# AC_REMOTE.net
KiCad netlist of a schematic drawn in Altium Designer
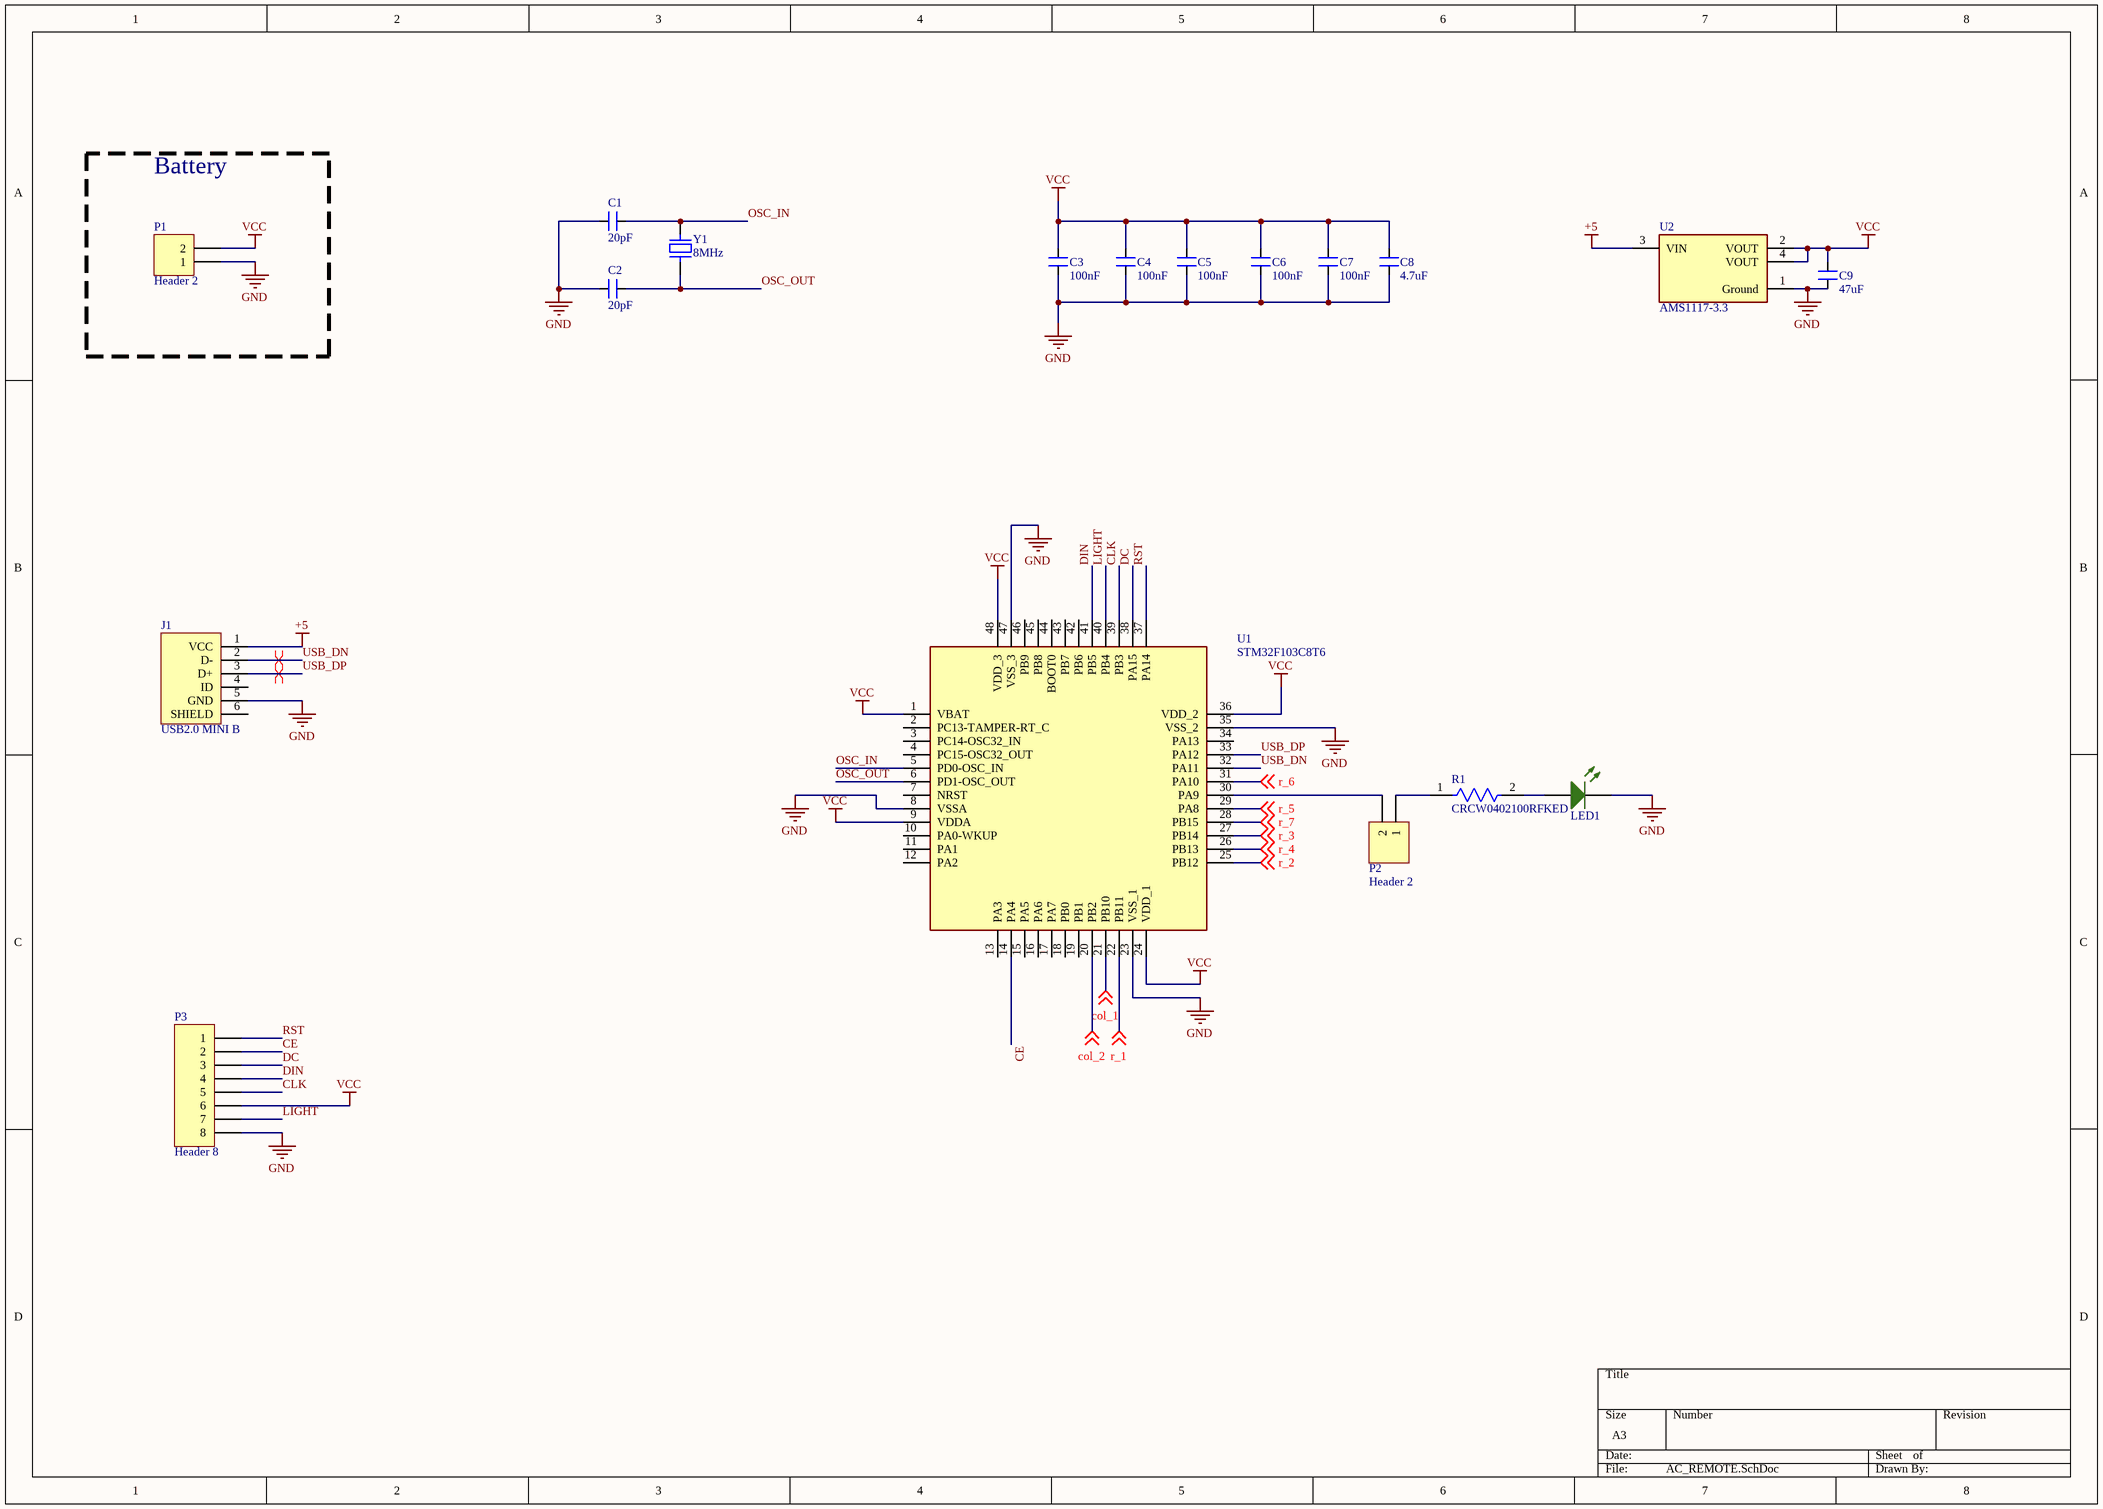
[diagram p0: AC_REMOTE.SchDoc]

(export (version "E")
  (design (tool "Eeschema 10.0.6"))
  (components
    (comp (ref "C1")
      (value "20pF")
      (footprint "CAP_0805")
      (description "±10% 50V Ceramic Capacitor C0G, NP0 0805 (2012 Metric)")
      (fields
        (field (name "MANUFACTURER") "AVX Corporation")
        (field (name "MANUFACTURER PART NUMBER") "08055A200KAT2A")
      )
      (libsource (lib "ESTEEMPCBLIB") (part "CAP_20pF-50V-10%-0805"))
    )
    (comp (ref "C2")
      (value "20pF")
      (footprint "CAP_0805")
      (description "±10% 50V Ceramic Capacitor C0G, NP0 0805 (2012 Metric)")
      (fields
        (field (name "MANUFACTURER") "AVX Corporation")
        (field (name "MANUFACTURER PART NUMBER") "08055A200KAT2A")
      )
      (libsource (lib "ESTEEMPCBLIB") (part "CAP_20pF-50V-10%-0805"))
    )
    (comp (ref "C3")
      (value "100nF")
      (footprint "CAP_0805")
      (description "100nF ±5% 50V Ceramic Capacitor C0G, NP0 0805 (2012 Metric)")
      (fields
        (field (name "MANUFACTURER") "KEMET")
        (field (name "MANUFACTURER PART NUMBER") "CC0805JRNPO9BN101")
      )
      (libsource (lib "ESTEEMPCBLIB") (part "CAP_100pF-50V-5%-0805"))
    )
    (comp (ref "C4")
      (value "100nF")
      (footprint "CAP_0805")
      (description "100nF ±5% 50V Ceramic Capacitor C0G, NP0 0805 (2012 Metric)")
      (fields
        (field (name "MANUFACTURER") "KEMET")
        (field (name "MANUFACTURER PART NUMBER") "CC0805JRNPO9BN101")
      )
      (libsource (lib "ESTEEMPCBLIB") (part "CAP_100pF-50V-5%-0805"))
    )
    (comp (ref "C5")
      (value "100nF")
      (footprint "CAP_0805")
      (description "100nF ±5% 50V Ceramic Capacitor C0G, NP0 0805 (2012 Metric)")
      (fields
        (field (name "MANUFACTURER") "KEMET")
        (field (name "MANUFACTURER PART NUMBER") "CC0805JRNPO9BN101")
      )
      (libsource (lib "ESTEEMPCBLIB") (part "CAP_100pF-50V-5%-0805"))
    )
    (comp (ref "C6")
      (value "100nF")
      (footprint "CAP_0805")
      (description "100nF ±5% 50V Ceramic Capacitor C0G, NP0 0805 (2012 Metric)")
      (fields
        (field (name "MANUFACTURER") "KEMET")
        (field (name "MANUFACTURER PART NUMBER") "CC0805JRNPO9BN101")
      )
      (libsource (lib "ESTEEMPCBLIB") (part "CAP_100pF-50V-5%-0805"))
    )
    (comp (ref "C7")
      (value "100nF")
      (footprint "CAP_0805")
      (description "100nF ±5% 50V Ceramic Capacitor C0G, NP0 0805 (2012 Metric)")
      (fields
        (field (name "MANUFACTURER") "KEMET")
        (field (name "MANUFACTURER PART NUMBER") "CC0805JRNPO9BN101")
      )
      (libsource (lib "ESTEEMPCBLIB") (part "CAP_100pF-50V-5%-0805"))
    )
    (comp (ref "C8")
      (value "4.7uF")
      (footprint "CAP_0805")
      (description "4.7µF ±10% 50V Ceramic Capacitor X5R 0805 (2012 Metric)")
      (fields
        (field (name "MANUFACTURER") "Yageo")
        (field (name "MANUFACTURER PART NUMBER") "GRM21BR61H475KE51L")
      )
      (libsource (lib "ESTEEMPCBLIB") (part "CAP_4.7uF-50V-10%-0805"))
    )
    (comp (ref "C9")
      (value "47uF")
      (footprint "CAP_0805")
      (description "47uF ±5% 50V Ceramic Capacitor C0G, NP0 0805 (2012 Metric)")
      (fields
        (field (name "MANUFACTURER") "KEMET")
        (field (name "MANUFACTURER PART NUMBER") "C0805C470J5GACTU")
      )
      (libsource (lib "ESTEEMPCBLIB") (part "CAP_47pF-50V-5%-0805"))
    )
    (comp (ref "J1")
      (value "USB2.0 MINI B")
      (footprint "CON_690-005-299-043")
      (description "USB - mini B USB 2.0 Receptacle Connector 5 Position Surface Mount, Right Angle")
      (fields
        (field (name "MANUFACTURER") "EDAC")
        (field (name "MANUFACTURER PART NUMBER") "690-005-299-043")
      )
      (libsource (lib "ESTEEMPCBLIB") (part "CON_USB2.0-MINIB-SMD"))
    )
    (comp (ref "LED1")
      (value "LED THD 5mm GREEN")
      (footprint "LED_5MM_GREEN")
      (libsource (lib "Led") (part "LED THD 5mm GREEN"))
    )
    (comp (ref "P1")
      (value "Header 2")
      (footprint "HDR1X2")
      (description "Header, 2-Pin")
      (fields (field (name "PUBLISHER") "Altium Limited"))
      (libsource (lib "") (part "Header 2_1"))
    )
    (comp (ref "P2")
      (value "Header 2")
      (footprint "HDR1X2")
      (description "Header, 2-Pin")
      (fields (field (name "PUBLISHER") "Altium Limited"))
      (libsource (lib "Miscellaneous Connectors") (part "Header 2"))
    )
    (comp (ref "P3")
      (value "Header 8")
      (footprint "HDR1X8")
      (description "Header, 8-Pin")
      (fields (field (name "PUBLISHER") "Altium Limited"))
      (libsource (lib "Miscellaneous Connectors") (part "Header 8"))
    )
    (comp (ref "R1")
      (value "CRCW0402100RFKED")
      (footprint "FP-CRCW0402-e3-IPC_C")
      (description "RES Thick Film, 100Ω, 1%, 0.063W, 100ppm/°C, 0402")
      (fields (field (name "TOLERANCE") "1%"))
      (libsource (lib "Altium Content Vault") (part "1029c3af85768c4190bb7ad29bc67b5"))
    )
    (comp (ref "U1")
      (value "STM32F103C8T6")
      (footprint "LQFP-48_19.6_393_58X11_SMD")
      (description "ARM® Cortex®-M3 STM32F1 Microcontroller IC 32-Bit 72MHz 64KB (64K x 8) FLASH 48-LQFP (7x7)")
      (fields (field (name "MANUFACTURER") "STMicroelectronics"))
      (libsource (lib "ESTEEMPCBLIB") (part "IC_STM32F103C8T6"))
    )
    (comp (ref "U2")
      (value "AMS1117-3.3")
      (footprint "FP-AMS1117-IPC_C")
      (description "LDO Voltage Regulators 1A, 3.3V")
      (fields
        (field (name "OCTOPART") "https://octopart.com/ams1117-3.3-advanced+monolithic+systems-25899300")
        (field (name "MANUFACTURER") "Advanced Monolithic Systems")
      )
      (libsource (lib "Altium Content Vault") (part "8bdbb5f8e77002000e30dd2845d0354"))
    )
    (comp (ref "Y1")
      (value "8MHz")
      (footprint "HC-49S SMD")
      (description "SMT Crystal")
      (fields (field (name "PARTNUMBER") "ABLS-8.000MHZ-K4T"))
      (libsource (lib "Xtal") (part "Crystal HC-49S SMD 8MHz"))
    )
  )
  (nets
    (net (code "1") (name "+5") (class "Default")
      (node (ref "J1") (pin "1") (pinfunction "VCC_1") (pintype "passive"))
      (node (ref "U2") (pin "3") (pinfunction "VIN_3") (pintype "power_in"))
    )
    (net (code "2") (name "/CE") (class "Default")
      (node (ref "P3") (pin "2") (pinfunction "2_2") (pintype "passive"))
      (node (ref "U1") (pin "14") (pinfunction "PA4_14") (pintype "passive"))
    )
    (net (code "3") (name "/CLK") (class "Default")
      (node (ref "P3") (pin "5") (pinfunction "5_5") (pintype "passive"))
      (node (ref "U1") (pin "39") (pinfunction "PB3_39") (pintype "passive"))
    )
    (net (code "4") (name "/DC") (class "Default")
      (node (ref "P3") (pin "3") (pinfunction "3_3") (pintype "passive"))
      (node (ref "U1") (pin "38") (pinfunction "PA15_38") (pintype "passive"))
    )
    (net (code "5") (name "/DIN") (class "Default")
      (node (ref "P3") (pin "4") (pinfunction "4_4") (pintype "passive"))
      (node (ref "U1") (pin "41") (pinfunction "PB5_41") (pintype "passive"))
    )
    (net (code "6") (name "/LIGHT") (class "Default")
      (node (ref "P3") (pin "7") (pinfunction "7_7") (pintype "passive"))
      (node (ref "U1") (pin "40") (pinfunction "PB4_40") (pintype "passive"))
    )
    (net (code "7") (name "/OSC_IN") (class "Default")
      (node (ref "C1") (pin "2") (pinfunction "2_2") (pintype "passive"))
      (node (ref "U1") (pin "5") (pinfunction "PD0-OSC_IN_5") (pintype "passive"))
      (node (ref "Y1") (pin "2") (pinfunction "2_2") (pintype "passive"))
    )
    (net (code "8") (name "/OSC_OUT") (class "Default")
      (node (ref "C2") (pin "2") (pinfunction "2_2") (pintype "passive"))
      (node (ref "U1") (pin "6") (pinfunction "PD1-OSC_OUT_6") (pintype "passive"))
      (node (ref "Y1") (pin "1") (pinfunction "1_1") (pintype "passive"))
    )
    (net (code "9") (name "/RST") (class "Default")
      (node (ref "P3") (pin "1") (pinfunction "1_1") (pintype "passive"))
      (node (ref "U1") (pin "37") (pinfunction "PA14_37") (pintype "passive"))
    )
    (net (code "10") (name "/USB_DN") (class "Default")
      (node (ref "J1") (pin "2") (pinfunction "D-_2") (pintype "passive"))
      (node (ref "U1") (pin "32") (pinfunction "PA11_32") (pintype "passive"))
    )
    (net (code "11") (name "/USB_DP") (class "Default")
      (node (ref "J1") (pin "3") (pinfunction "D+_3") (pintype "passive"))
      (node (ref "U1") (pin "33") (pinfunction "PA12_33") (pintype "passive"))
    )
    (net (code "12") (name "GND") (class "Default")
      (node (ref "C1") (pin "1") (pinfunction "1_1") (pintype "passive"))
      (node (ref "C2") (pin "1") (pinfunction "1_1") (pintype "passive"))
      (node (ref "C3") (pin "1") (pinfunction "1_1") (pintype "passive"))
      (node (ref "C4") (pin "1") (pinfunction "1_1") (pintype "passive"))
      (node (ref "C5") (pin "1") (pinfunction "1_1") (pintype "passive"))
      (node (ref "C6") (pin "1") (pinfunction "1_1") (pintype "passive"))
      (node (ref "C7") (pin "1") (pinfunction "1_1") (pintype "passive"))
      (node (ref "C8") (pin "2") (pinfunction "2_2") (pintype "passive"))
      (node (ref "C9") (pin "1") (pinfunction "1_1") (pintype "passive"))
      (node (ref "J1") (pin "5") (pinfunction "GND_5") (pintype "passive"))
      (node (ref "LED1") (pin "2") (pinfunction "K_2") (pintype "passive"))
      (node (ref "P1") (pin "1") (pinfunction "1_1") (pintype "passive"))
      (node (ref "P3") (pin "8") (pinfunction "8_8") (pintype "passive"))
      (node (ref "U1") (pin "23") (pinfunction "VSS_1_23") (pintype "passive"))
      (node (ref "U1") (pin "35") (pinfunction "VSS_2_35") (pintype "passive"))
      (node (ref "U1") (pin "47") (pinfunction "VSS_3_47") (pintype "passive"))
      (node (ref "U1") (pin "8") (pinfunction "VSSA_8") (pintype "passive"))
      (node (ref "U2") (pin "1") (pinfunction "Ground_1") (pintype "power_in"))
    )
    (net (code "13") (name "Net-(LED1-A)") (class "Default")
      (node (ref "LED1") (pin "1") (pinfunction "A_1") (pintype "passive"))
      (node (ref "R1") (pin "2") (pinfunction "2_2") (pintype "passive"))
    )
    (net (code "14") (name "Net-(P2-Pad1)") (class "Default")
      (node (ref "P2") (pin "1") (pinfunction "1_1") (pintype "passive"))
      (node (ref "R1") (pin "1") (pinfunction "1_1") (pintype "passive"))
    )
    (net (code "15") (name "Net-(U1-PA9)") (class "Default")
      (node (ref "P2") (pin "2") (pinfunction "2_2") (pintype "passive"))
      (node (ref "U1") (pin "30") (pinfunction "PA9_30") (pintype "passive"))
    )
    (net (code "16") (name "VCC") (class "Default")
      (node (ref "C3") (pin "2") (pinfunction "2_2") (pintype "passive"))
      (node (ref "C4") (pin "2") (pinfunction "2_2") (pintype "passive"))
      (node (ref "C5") (pin "2") (pinfunction "2_2") (pintype "passive"))
      (node (ref "C6") (pin "2") (pinfunction "2_2") (pintype "passive"))
      (node (ref "C7") (pin "2") (pinfunction "2_2") (pintype "passive"))
      (node (ref "C8") (pin "1") (pinfunction "1_1") (pintype "passive"))
      (node (ref "C9") (pin "2") (pinfunction "2_2") (pintype "passive"))
      (node (ref "P1") (pin "2") (pinfunction "2_2") (pintype "passive"))
      (node (ref "P3") (pin "6") (pinfunction "6_6") (pintype "passive"))
      (node (ref "U1") (pin "1") (pinfunction "VBAT_1") (pintype "passive"))
      (node (ref "U1") (pin "24") (pinfunction "VDD_1_24") (pintype "passive"))
      (node (ref "U1") (pin "36") (pinfunction "VDD_2_36") (pintype "passive"))
      (node (ref "U1") (pin "48") (pinfunction "VDD_3_48") (pintype "passive"))
      (node (ref "U1") (pin "9") (pinfunction "VDDA_9") (pintype "passive"))
      (node (ref "U2") (pin "2") (pinfunction "VOUT_2") (pintype "passive"))
      (node (ref "U2") (pin "4") (pinfunction "VOUT_4") (pintype "passive"))
    )
    (net (code "17") (name "col_1") (class "Default")
      (node (ref "U1") (pin "21") (pinfunction "PB10_21") (pintype "passive"))
    )
    (net (code "18") (name "col_2") (class "Default")
      (node (ref "U1") (pin "20") (pinfunction "PB2_20") (pintype "passive"))
    )
    (net (code "19") (name "r_1") (class "Default")
      (node (ref "U1") (pin "22") (pinfunction "PB11_22") (pintype "passive"))
    )
    (net (code "20") (name "r_2") (class "Default")
      (node (ref "U1") (pin "25") (pinfunction "PB12_25") (pintype "passive"))
    )
    (net (code "21") (name "r_3") (class "Default")
      (node (ref "U1") (pin "27") (pinfunction "PB14_27") (pintype "passive"))
    )
    (net (code "22") (name "r_4") (class "Default")
      (node (ref "U1") (pin "26") (pinfunction "PB13_26") (pintype "passive"))
    )
    (net (code "23") (name "r_5") (class "Default")
      (node (ref "U1") (pin "29") (pinfunction "PA8_29") (pintype "passive"))
    )
    (net (code "24") (name "r_6") (class "Default")
      (node (ref "U1") (pin "31") (pinfunction "PA10_31") (pintype "passive"))
    )
    (net (code "25") (name "r_7") (class "Default")
      (node (ref "U1") (pin "28") (pinfunction "PB15_28") (pintype "passive"))
    )
    (net (code "26") (name "unconnected-(J1-ID-Pad4)") (class "Default")
      (node (ref "J1") (pin "4") (pinfunction "ID_4") (pintype "passive"))
    )
    (net (code "27") (name "unconnected-(J1-SHIELD-Pad6)") (class "Default")
      (node (ref "J1") (pin "6") (pinfunction "SHIELD_6") (pintype "passive"))
    )
    (net (code "28") (name "unconnected-(U1-BOOT0-Pad44)") (class "Default")
      (node (ref "U1") (pin "44") (pinfunction "BOOT0_44") (pintype "passive"))
    )
    (net (code "29") (name "unconnected-(U1-NRST-Pad7)") (class "Default")
      (node (ref "U1") (pin "7") (pinfunction "NRST_7") (pintype "passive"))
    )
    (net (code "30") (name "unconnected-(U1-PA0-WKUP-Pad10)") (class "Default")
      (node (ref "U1") (pin "10") (pinfunction "PA0-WKUP_10") (pintype "passive"))
    )
    (net (code "31") (name "unconnected-(U1-PA1-Pad11)") (class "Default")
      (node (ref "U1") (pin "11") (pinfunction "PA1_11") (pintype "passive"))
    )
    (net (code "32") (name "unconnected-(U1-PA2-Pad12)") (class "Default")
      (node (ref "U1") (pin "12") (pinfunction "PA2_12") (pintype "passive"))
    )
    (net (code "33") (name "unconnected-(U1-PA3-Pad13)") (class "Default")
      (node (ref "U1") (pin "13") (pinfunction "PA3_13") (pintype "passive"))
    )
    (net (code "34") (name "unconnected-(U1-PA5-Pad15)") (class "Default")
      (node (ref "U1") (pin "15") (pinfunction "PA5_15") (pintype "passive"))
    )
    (net (code "35") (name "unconnected-(U1-PA6-Pad16)") (class "Default")
      (node (ref "U1") (pin "16") (pinfunction "PA6_16") (pintype "passive"))
    )
    (net (code "36") (name "unconnected-(U1-PA7-Pad17)") (class "Default")
      (node (ref "U1") (pin "17") (pinfunction "PA7_17") (pintype "passive"))
    )
    (net (code "37") (name "unconnected-(U1-PA13-Pad34)") (class "Default")
      (node (ref "U1") (pin "34") (pinfunction "PA13_34") (pintype "passive"))
    )
    (net (code "38") (name "unconnected-(U1-PB0-Pad18)") (class "Default")
      (node (ref "U1") (pin "18") (pinfunction "PB0_18") (pintype "passive"))
    )
    (net (code "39") (name "unconnected-(U1-PB1-Pad19)") (class "Default")
      (node (ref "U1") (pin "19") (pinfunction "PB1_19") (pintype "passive"))
    )
    (net (code "40") (name "unconnected-(U1-PB6-Pad42)") (class "Default")
      (node (ref "U1") (pin "42") (pinfunction "PB6_42") (pintype "passive"))
    )
    (net (code "41") (name "unconnected-(U1-PB7-Pad43)") (class "Default")
      (node (ref "U1") (pin "43") (pinfunction "PB7_43") (pintype "passive"))
    )
    (net (code "42") (name "unconnected-(U1-PB8-Pad45)") (class "Default")
      (node (ref "U1") (pin "45") (pinfunction "PB8_45") (pintype "passive"))
    )
    (net (code "43") (name "unconnected-(U1-PB9-Pad46)") (class "Default")
      (node (ref "U1") (pin "46") (pinfunction "PB9_46") (pintype "passive"))
    )
    (net (code "44") (name "unconnected-(U1-PC13-TAMPER-RT_C-Pad2)") (class "Default")
      (node (ref "U1") (pin "2") (pinfunction "PC13-TAMPER-RT_C_2") (pintype "passive"))
    )
    (net (code "45") (name "unconnected-(U1-PC14-OSC32_IN-Pad3)") (class "Default")
      (node (ref "U1") (pin "3") (pinfunction "PC14-OSC32_IN_3") (pintype "passive"))
    )
    (net (code "46") (name "unconnected-(U1-PC15-OSC32_OUT-Pad4)") (class "Default")
      (node (ref "U1") (pin "4") (pinfunction "PC15-OSC32_OUT_4") (pintype "passive"))
    )
  )
)
